# Filter-17.net
KiCad netlist of a schematic drawn in Altium Designer
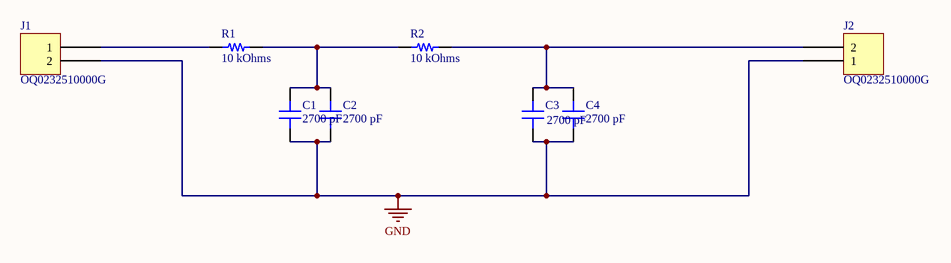
[diagram p0: Filter-17.SchDoc]

(export (version "E")
  (design (tool "Eeschema 10.0.6"))
  (components
    (comp (ref "C1")
      (value "2700 pF")
      (footprint "CAP 0603_1608")
      (description "CAP CER 2700PF 25V NP0 0603")
      (fields (field (name "PART NUMBER") "C0603C272F3GAC7867") (field (name "MANUFACTURER") "KEMET"))
      (libsource (lib "Celestial Altium Library - altium_library") (part "Capacitor"))
    )
    (comp (ref "C2")
      (value "2700 pF")
      (footprint "CAP 0603_1608")
      (description "CAP CER 2700PF 25V NP0 0603")
      (fields (field (name "PART NUMBER") "C0603C272F3GAC7867") (field (name "MANUFACTURER") "KEMET"))
      (libsource (lib "Celestial Altium Library - altium_library") (part "Capacitor"))
    )
    (comp (ref "C3")
      (value "2700 pF")
      (footprint "CAP 0603_1608")
      (description "CAP CER 2700PF 25V NP0 0603")
      (fields (field (name "PART NUMBER") "C0603C272F3GAC7867") (field (name "MANUFACTURER") "KEMET"))
      (libsource (lib "Celestial Altium Library - altium_library") (part "Capacitor"))
    )
    (comp (ref "C4")
      (value "2700 pF")
      (footprint "CAP 0603_1608")
      (description "CAP CER 2700PF 25V NP0 0603")
      (fields (field (name "PART NUMBER") "C0603C272F3GAC7867") (field (name "MANUFACTURER") "KEMET"))
      (libsource (lib "Celestial Altium Library - altium_library") (part "Capacitor"))
    )
    (comp (ref "J1")
      (value "OQ0232510000G")
      (footprint "FCI 06-381-2PIN")
      (description "TERM BLOCK HDR 2POS 90DEG 3.81MM")
      (fields (field (name "MANUFACTURER") "Amphenol Anytek"))
      (libsource (lib "") (part "2 Pin_1"))
    )
    (comp (ref "J2")
      (value "OQ0232510000G")
      (footprint "FCI 06-381-2PIN")
      (description "TERM BLOCK HDR 2POS 90DEG 3.81MM")
      (fields (field (name "MANUFACTURER") "Amphenol Anytek"))
      (libsource (lib "Celestial Altium Library - altium_library") (part "2 Pin"))
    )
    (comp (ref "R1")
      (value "10 kOhms")
      (footprint "RES 0603_1608")
      (description "RES 10K OHM 0.1% 1/16W 0603")
      (fields
        (field (name "PART NUMBER") "RNCS0603BKE10K0")
        (field (name "MANUFACTURER") "Stackpole Electronics Inc")
      )
      (libsource (lib "Celestial Altium Library - altium_library") (part "Resistor"))
    )
    (comp (ref "R2")
      (value "10 kOhms")
      (footprint "RES 0603_1608")
      (description "RES 10K OHM 0.1% 1/16W 0603")
      (fields
        (field (name "PART NUMBER") "RNCS0603BKE10K0")
        (field (name "MANUFACTURER") "Stackpole Electronics Inc")
      )
      (libsource (lib "Celestial Altium Library - altium_library") (part "Resistor"))
    )
  )
  (nets
    (net (code "1") (name "GND") (class "Default")
      (node (ref "C1") (pin "1") (pinfunction "1_1") (pintype "passive"))
      (node (ref "C2") (pin "1") (pinfunction "1_1") (pintype "passive"))
      (node (ref "C3") (pin "1") (pinfunction "1_1") (pintype "passive"))
      (node (ref "C4") (pin "1") (pinfunction "1_1") (pintype "passive"))
      (node (ref "J1") (pin "2") (pinfunction "2_2") (pintype "passive"))
      (node (ref "J2") (pin "1") (pinfunction "1_1") (pintype "passive"))
    )
    (net (code "2") (name "Net-(C1-Pad2)") (class "Default")
      (node (ref "C1") (pin "2") (pinfunction "2_2") (pintype "passive"))
      (node (ref "C2") (pin "2") (pinfunction "2_2") (pintype "passive"))
      (node (ref "R1") (pin "2") (pinfunction "2_2") (pintype "passive"))
      (node (ref "R2") (pin "1") (pinfunction "1_1") (pintype "passive"))
    )
    (net (code "3") (name "Net-(C3-Pad2)") (class "Default")
      (node (ref "C3") (pin "2") (pinfunction "2_2") (pintype "passive"))
      (node (ref "C4") (pin "2") (pinfunction "2_2") (pintype "passive"))
      (node (ref "J2") (pin "2") (pinfunction "2_2") (pintype "passive"))
      (node (ref "R2") (pin "2") (pinfunction "2_2") (pintype "passive"))
    )
    (net (code "4") (name "Net-(J1-Pad1)") (class "Default")
      (node (ref "J1") (pin "1") (pinfunction "1_1") (pintype "passive"))
      (node (ref "R1") (pin "1") (pinfunction "1_1") (pintype "passive"))
    )
  )
)
